# PS.net
KiCad netlist of a schematic drawn in Altium Designer
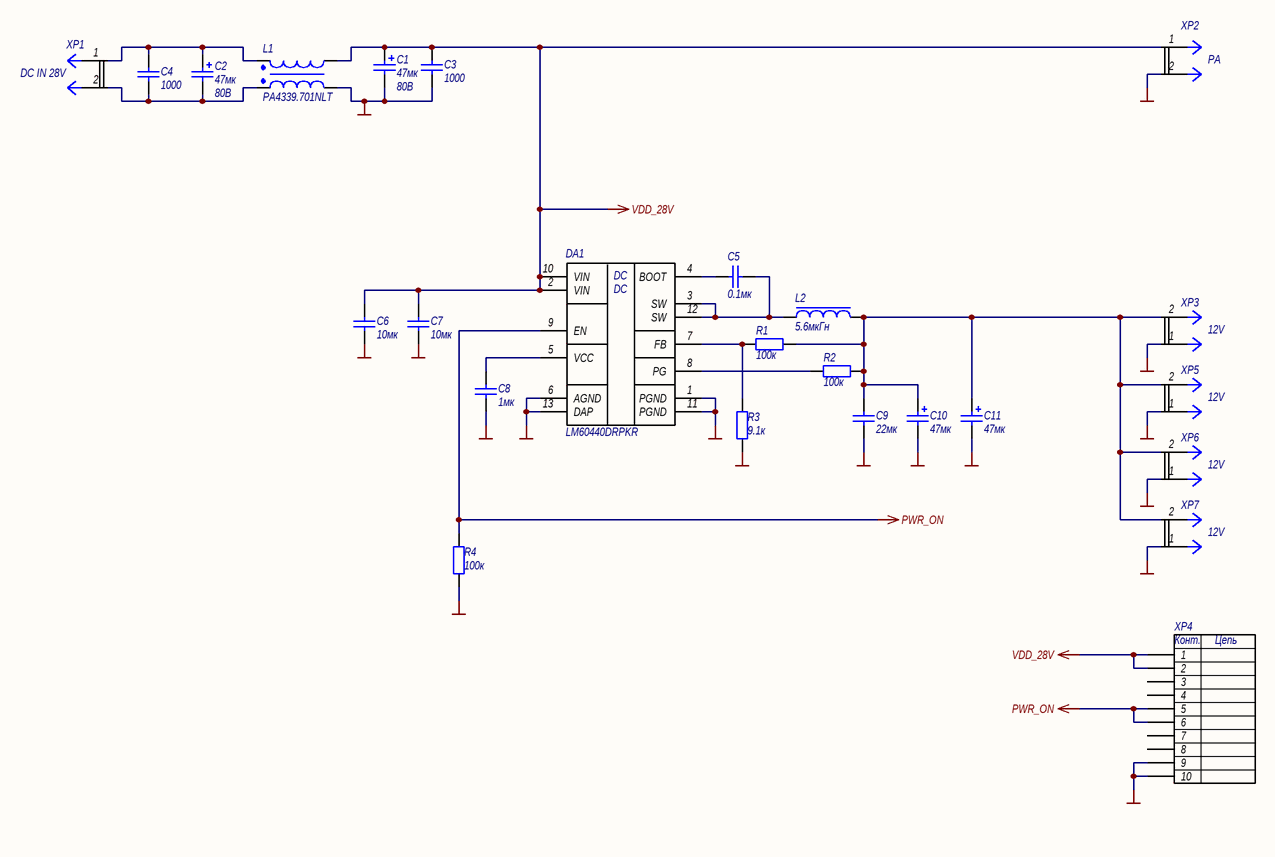
[diagram p0: PS.SchDoc]

(export (version "E")
  (design (tool "Eeschema 10.0.6"))
  (components
    (comp (ref "C1")
      (value "47мк")
      (footprint "CAPAE116103X105N")
      (description "Гибридный ЧИП-конденсатор")
      (fields
        (field (name "TOLERANCE") "±20%")
        (field (name "MANUFACTURERPARTNUMBER") "EEHZC1K470V")
        (field (name "POWER/VOLTAGE") "80В")
        (field (name "PUBLISHER") "Altium Limited")
      )
      (libsource (lib "nels_caps") (part "Конденсатор гибридный SMD 47мкФ ±20% 80В"))
    )
    (comp (ref "C2")
      (value "47мк")
      (footprint "CAPAE116103X105N")
      (description "Гибридный ЧИП-конденсатор")
      (fields
        (field (name "TOLERANCE") "±20%")
        (field (name "MANUFACTURERPARTNUMBER") "EEHZC1K470V")
        (field (name "POWER/VOLTAGE") "80В")
        (field (name "PUBLISHER") "Altium Limited")
      )
      (libsource (lib "nels_caps") (part "Конденсатор гибридный SMD 47мкФ ±20% 80В"))
    )
    (comp (ref "C3")
      (value "1000")
      (footprint "CAPC2012X12L")
      (description "Кер. ЧИП-конденсатор")
      (fields (field (name "MANUFACTURER") "WALSIN") (field (name "TOLERANCE") "±10%"))
      (libsource (lib "nels_caps") (part "Кер.ЧИП конд. 0805 1000пФ X7R 10% 100В"))
    )
    (comp (ref "C4")
      (value "1000")
      (footprint "CAPC2012X12L")
      (description "Кер. ЧИП-конденсатор")
      (fields (field (name "MANUFACTURER") "WALSIN") (field (name "TOLERANCE") "±10%"))
      (libsource (lib "nels_caps") (part "Кер.ЧИП конд. 0805 1000пФ X7R 10% 100В"))
    )
    (comp (ref "C5")
      (value "0.1мк")
      (footprint "CAPC1005X06N")
      (description "Кер. ЧИП-конденсатор")
      (fields (field (name "TOLERANCE") "±10%"))
      (libsource (lib "nels") (part "Кер.ЧИП конд. 0402 0.1мкФ X7R 10%, 16В"))
    )
    (comp (ref "C6")
      (value "10мк")
      (footprint "CAPC3225X27L")
      (description "Кер. ЧИП-конденсатор")
      (fields (field (name "MANUFACTURER") "Murata") (field (name "TOLERANCE") "±20%"))
      (libsource (lib "nels") (part "Кер.ЧИП конд. 1210 10мкФ X5R 20% 50В"))
    )
    (comp (ref "C7")
      (value "10мк")
      (footprint "CAPC3225X27L")
      (description "Кер. ЧИП-конденсатор")
      (fields (field (name "MANUFACTURER") "Murata") (field (name "TOLERANCE") "±20%"))
      (libsource (lib "nels") (part "Кер.ЧИП конд. 1210 10мкФ X5R 20% 50В"))
    )
    (comp (ref "C8")
      (value "1мк")
      (footprint "CAPC1005X06N")
      (description "Кер. ЧИП-конденсатор")
      (fields (field (name "TOLERANCE") "±10%"))
      (libsource (lib "nels_caps") (part "Кер.ЧИП конд. 0402 1мкФ X5R 10%, 10В"))
    )
    (comp (ref "C9")
      (value "22мк")
      (footprint "CAPC2012X12L")
      (description "Кер. ЧИП-конденсатор")
      (fields (field (name "MANUFACTURER") "TDK") (field (name "TOLERANCE") "±10%"))
      (libsource (lib "nels_caps") (part "Кер.ЧИП конд. 0805 22мкФ X5R 10% 16В"))
    )
    (comp (ref "C10")
      (value "47мк")
      (footprint "CAPMP7343X28L")
      (description "Тант. ЧИП-конденсатор")
      (fields (field (name "TOLERANCE") "±10%") (field (name "PUBLISHER") "Altium Limited"))
      (libsource (lib "nels_caps") (part "Конденсатор танталовый SMD D case 47мкФ ±10% 25B"))
    )
    (comp (ref "C11")
      (value "47мк")
      (footprint "CAPMP7343X28L")
      (description "Тант. ЧИП-конденсатор")
      (fields (field (name "TOLERANCE") "±10%") (field (name "PUBLISHER") "Altium Limited"))
      (libsource (lib "nels_caps") (part "Конденсатор танталовый SMD D case 47мкФ ±10% 25B"))
    )
    (comp (ref "DA1")
      (value "LM60440DRPKR")
      (footprint "WQFN-13")
      (description "3.8-V to 36-V, 4-A Ultra-Small Synchronous Step-Down Converter")
      (libsource (lib "nels_chip") (part "Микросхема LM60440DRPKR"))
    )
    (comp (ref "L1")
      (value "PA4339.701NLT")
      (footprint "HCCI-80-2")
      (description "SMT Common Mode Choke")
      (fields (field (name "MANUFACTURER") "Pulse"))
      (libsource (lib "nels_ind") (part "ЧИП синфазный фильтр PG1265NL"))
    )
    (comp (ref "L2")
      (value "5.6мкГн")
      (footprint "Coilcraft-XAL5030")
      (description "Shielded Power Inductor – XAL5030")
      (fields
        (field (name "MANUFACTURER") "Сoilcraft")
        (field (name "MANUFACTURERPARTNUMBER") "XAL5030-222MEB")
      )
      (libsource (lib "nels_ind") (part "ЧИП индуктивность XAL5030-562MEB"))
    )
    (comp (ref "R1")
      (value "100к")
      (footprint "RESC1005X06N")
      (description "ЧИП-резистор")
      (fields (field (name "TOLERANCE") "±5%"))
      (libsource (lib "nels_res") (part "Чип резистор 0402 100 кОм, 5%"))
    )
    (comp (ref "R2")
      (value "100к")
      (footprint "RESC1005X06N")
      (description "ЧИП-резистор")
      (fields (field (name "TOLERANCE") "±5%"))
      (libsource (lib "nels_res") (part "Чип резистор 0402 100 кОм, 5%"))
    )
    (comp (ref "R3")
      (value "9.1к")
      (footprint "RESC1005X06N")
      (description "ЧИП-резистор")
      (fields (field (name "TOLERANCE") "±5%"))
      (libsource (lib "nels_res") (part "Чип резистор 0402 9,1 кОм, 5%"))
    )
    (comp (ref "R4")
      (value "100к")
      (footprint "RESC1005X06N")
      (description "ЧИП-резистор")
      (fields (field (name "TOLERANCE") "±5%"))
      (libsource (lib "") (part "Чип резистор 0402 100 кОм, 5%_1"))
    )
    (comp (ref "XP1")
      (value "XT60-F")
      (footprint "XT60-F")
      (description "AMASS XT60-F")
      (libsource (lib "nels_conn") (part "Соединитель XT60-F"))
    )
    (comp (ref "XP2")
      (value "XT60-F")
      (footprint "XT60-F")
      (description "AMASS XT60-F")
      (libsource (lib "nels_conn") (part "Соединитель XT60-F"))
    )
    (comp (ref "XP3")
      (value "XT30UPB-M")
      (footprint "XT30UPB-M")
      (description "AMASS XT30UPB-M  5 mm")
      (libsource (lib "nels_conn") (part "Соединитель XT30UPB-M"))
    )
    (comp (ref "XP4")
      (value "FH12-10S-0.5SVA")
      (footprint "FH12-10S-0.5SH")
      (description "0.5mm  Pitch FPC/FFC Connector FH12 Series")
      (fields (field (name "MANUFACTURER") "Hirose"))
      (libsource (lib "nels_conn") (part "Соединитель FH12-10S-0.5SVA"))
    )
    (comp (ref "XP5")
      (value "XT30UPB-M")
      (footprint "XT30UPB-M")
      (description "AMASS XT30UPB-M  5 mm")
      (libsource (lib "nels_conn") (part "Соединитель XT30UPB-M"))
    )
    (comp (ref "XP6")
      (value "XT30UPB-M")
      (footprint "XT30UPB-M")
      (description "AMASS XT30UPB-M  5 mm")
      (libsource (lib "nels_conn") (part "Соединитель XT30UPB-M"))
    )
    (comp (ref "XP7")
      (value "XT30UPB-M")
      (footprint "XT30UPB-M")
      (description "AMASS XT30UPB-M  5 mm")
      (libsource (lib "nels_conn") (part "Соединитель XT30UPB-M"))
    )
  )
  (nets
    (net (code "1") (name "GND") (class "Default")
      (node (ref "C1") (pin "2") (pinfunction "2_2") (pintype "passive"))
      (node (ref "C10") (pin "2") (pinfunction "2_2") (pintype "passive"))
      (node (ref "C11") (pin "2") (pinfunction "2_2") (pintype "passive"))
      (node (ref "C3") (pin "1") (pinfunction "1_1") (pintype "passive"))
      (node (ref "C6") (pin "1") (pinfunction "1_1") (pintype "passive"))
      (node (ref "C7") (pin "1") (pinfunction "1_1") (pintype "passive"))
      (node (ref "C8") (pin "1") (pinfunction "1_1") (pintype "passive"))
      (node (ref "C9") (pin "1") (pinfunction "1_1") (pintype "passive"))
      (node (ref "DA1") (pin "1") (pinfunction "PGND_1") (pintype "passive"))
      (node (ref "DA1") (pin "11") (pinfunction "PGND_11") (pintype "passive"))
      (node (ref "DA1") (pin "13") (pinfunction "DAP_13") (pintype "passive"))
      (node (ref "DA1") (pin "6") (pinfunction "AGND_6") (pintype "passive"))
      (node (ref "L1") (pin "3") (pinfunction "3_3") (pintype "passive"))
      (node (ref "R3") (pin "2") (pinfunction "2_2") (pintype "passive"))
      (node (ref "R4") (pin "2") (pinfunction "2_2") (pintype "passive"))
      (node (ref "XP2") (pin "2") (pinfunction "~_2") (pintype "passive"))
      (node (ref "XP3") (pin "1") (pinfunction "~_1") (pintype "passive"))
      (node (ref "XP4") (pin "10") (pinfunction "10_10") (pintype "passive"))
      (node (ref "XP4") (pin "9") (pinfunction "9_9") (pintype "passive"))
      (node (ref "XP5") (pin "1") (pinfunction "~_1") (pintype "passive"))
      (node (ref "XP6") (pin "1") (pinfunction "~_1") (pintype "passive"))
      (node (ref "XP7") (pin "1") (pinfunction "~_1") (pintype "passive"))
    )
    (net (code "2") (name "Net-(C2-Pad1)") (class "Default")
      (node (ref "C2") (pin "1") (pinfunction "1_1") (pintype "passive"))
      (node (ref "C4") (pin "2") (pinfunction "2_2") (pintype "passive"))
      (node (ref "L1") (pin "1") (pinfunction "1_1") (pintype "passive"))
      (node (ref "XP1") (pin "1") (pinfunction "~_1") (pintype "passive"))
    )
    (net (code "3") (name "Net-(C2-Pad2)") (class "Default")
      (node (ref "C2") (pin "2") (pinfunction "2_2") (pintype "passive"))
      (node (ref "C4") (pin "1") (pinfunction "1_1") (pintype "passive"))
      (node (ref "L1") (pin "2") (pinfunction "2_2") (pintype "passive"))
      (node (ref "XP1") (pin "2") (pinfunction "~_2") (pintype "passive"))
    )
    (net (code "4") (name "Net-(C5-Pad1)") (class "Default")
      (node (ref "C5") (pin "1") (pinfunction "1_1") (pintype "passive"))
      (node (ref "DA1") (pin "12") (pinfunction "SW_12") (pintype "passive"))
      (node (ref "DA1") (pin "3") (pinfunction "SW_3") (pintype "passive"))
      (node (ref "L2") (pin "1") (pinfunction "1_1") (pintype "passive"))
    )
    (net (code "5") (name "Net-(C10-Pad1)") (class "Default")
      (node (ref "C10") (pin "1") (pinfunction "1_1") (pintype "passive"))
      (node (ref "C11") (pin "1") (pinfunction "1_1") (pintype "passive"))
      (node (ref "C9") (pin "2") (pinfunction "2_2") (pintype "passive"))
      (node (ref "L2") (pin "2") (pinfunction "2_2") (pintype "passive"))
      (node (ref "R1") (pin "1") (pinfunction "1_1") (pintype "passive"))
      (node (ref "R2") (pin "1") (pinfunction "1_1") (pintype "passive"))
      (node (ref "XP3") (pin "2") (pinfunction "~_2") (pintype "passive"))
      (node (ref "XP5") (pin "2") (pinfunction "~_2") (pintype "passive"))
      (node (ref "XP6") (pin "2") (pinfunction "~_2") (pintype "passive"))
      (node (ref "XP7") (pin "2") (pinfunction "~_2") (pintype "passive"))
    )
    (net (code "6") (name "Net-(DA1-BOOT)") (class "Default")
      (node (ref "C5") (pin "2") (pinfunction "2_2") (pintype "passive"))
      (node (ref "DA1") (pin "4") (pinfunction "BOOT_4") (pintype "passive"))
    )
    (net (code "7") (name "Net-(DA1-FB)") (class "Default")
      (node (ref "DA1") (pin "7") (pinfunction "FB_7") (pintype "passive"))
      (node (ref "R1") (pin "2") (pinfunction "2_2") (pintype "passive"))
      (node (ref "R3") (pin "1") (pinfunction "1_1") (pintype "passive"))
    )
    (net (code "8") (name "Net-(DA1-PG)") (class "Default")
      (node (ref "DA1") (pin "8") (pinfunction "PG_8") (pintype "passive"))
      (node (ref "R2") (pin "2") (pinfunction "2_2") (pintype "passive"))
    )
    (net (code "9") (name "Net-(DA1-VCC)") (class "Default")
      (node (ref "C8") (pin "2") (pinfunction "2_2") (pintype "passive"))
      (node (ref "DA1") (pin "5") (pinfunction "VCC_5") (pintype "passive"))
    )
    (net (code "10") (name "PWR_ON") (class "Default")
      (node (ref "DA1") (pin "9") (pinfunction "EN_9") (pintype "passive"))
      (node (ref "R4") (pin "1") (pinfunction "1_1") (pintype "passive"))
      (node (ref "XP4") (pin "5") (pinfunction "5_5") (pintype "passive"))
      (node (ref "XP4") (pin "6") (pinfunction "6_6") (pintype "passive"))
    )
    (net (code "11") (name "VDD_28V") (class "Default")
      (node (ref "C1") (pin "1") (pinfunction "1_1") (pintype "passive"))
      (node (ref "C3") (pin "2") (pinfunction "2_2") (pintype "passive"))
      (node (ref "C6") (pin "2") (pinfunction "2_2") (pintype "passive"))
      (node (ref "C7") (pin "2") (pinfunction "2_2") (pintype "passive"))
      (node (ref "DA1") (pin "10") (pinfunction "VIN_10") (pintype "passive"))
      (node (ref "DA1") (pin "2") (pinfunction "VIN_2") (pintype "passive"))
      (node (ref "L1") (pin "4") (pinfunction "4_4") (pintype "passive"))
      (node (ref "XP2") (pin "1") (pinfunction "~_1") (pintype "passive"))
      (node (ref "XP4") (pin "1") (pinfunction "1_1") (pintype "passive"))
      (node (ref "XP4") (pin "2") (pinfunction "2_2") (pintype "passive"))
    )
    (net (code "12") (name "unconnected-(XP4-Pad3)") (class "Default")
      (node (ref "XP4") (pin "3") (pinfunction "3_3") (pintype "passive"))
    )
    (net (code "13") (name "unconnected-(XP4-Pad4)") (class "Default")
      (node (ref "XP4") (pin "4") (pinfunction "4_4") (pintype "passive"))
    )
    (net (code "14") (name "unconnected-(XP4-Pad7)") (class "Default")
      (node (ref "XP4") (pin "7") (pinfunction "7_7") (pintype "passive"))
    )
    (net (code "15") (name "unconnected-(XP4-Pad8)") (class "Default")
      (node (ref "XP4") (pin "8") (pinfunction "8_8") (pintype "passive"))
    )
  )
)
